# tiny84standalone.net
KiCad netlist of a schematic drawn in EAGLE
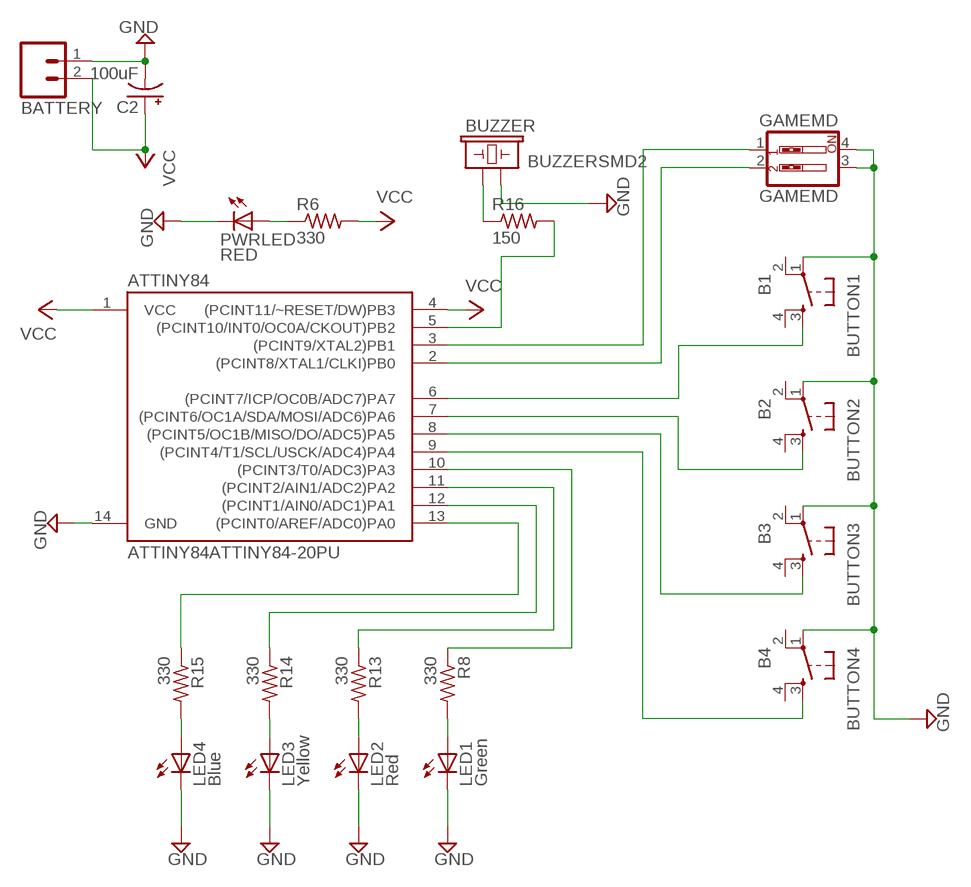
[diagram p0: schematic, sheet 1]

(export (version "E")
  (design (tool "Eeschema 10.0.6"))
  (components
    (comp (ref "ATTINY84")
      (value "ATTINY84ATTINY84-20PU")
      (footprint "eagle-import:DIL14")
      (libsource (lib "eagle-import") (part "ATTINY84ATTINY84-20PU"))
    )
    (comp (ref "BATTERY")
      (value "M02JST-PTH-VERT")
      (footprint "eagle-import:JST-2-PTH-VERT")
      (libsource (lib "eagle-import") (part "M02JST-PTH-VERT"))
    )
    (comp (ref "BUTTON1")
      (value "B1")
      (footprint "eagle-import:TACTILE-PTH")
      (libsource (lib "eagle-import") (part "TAC_SWITCHPTH"))
    )
    (comp (ref "BUTTON2")
      (value "B2")
      (footprint "eagle-import:TACTILE-PTH")
      (libsource (lib "eagle-import") (part "TAC_SWITCHPTH"))
    )
    (comp (ref "BUTTON3")
      (value "B3")
      (footprint "eagle-import:TACTILE-PTH")
      (libsource (lib "eagle-import") (part "TAC_SWITCHPTH"))
    )
    (comp (ref "BUTTON4")
      (value "B4")
      (footprint "eagle-import:TACTILE-PTH")
      (libsource (lib "eagle-import") (part "TAC_SWITCHPTH"))
    )
    (comp (ref "BUZZER")
      (value "BUZZERSMD2")
      (footprint "eagle-import:BUZZER-CCV")
      (libsource (lib "eagle-import") (part "BUZZERSMD2"))
    )
    (comp (ref "C2")
      (value "100uF")
      (footprint "eagle-import:CPOL-RADIAL-100UF-25V")
      (libsource (lib "eagle-import") (part "CAP_POLPTH1"))
    )
    (comp (ref "GAMEMD")
      (value "GAMEMD")
      (footprint "eagle-import:DIPSWITCH-02")
      (libsource (lib "eagle-import") (part "SW_DIP-2"))
    )
    (comp (ref "LED1")
      (value "Green")
      (footprint "eagle-import:LED5MM")
      (libsource (lib "eagle-import") (part "LED5MM"))
    )
    (comp (ref "LED2")
      (value "Red")
      (footprint "eagle-import:LED5MM")
      (libsource (lib "eagle-import") (part "LED5MM"))
    )
    (comp (ref "LED3")
      (value "Yellow")
      (footprint "eagle-import:LED5MM")
      (libsource (lib "eagle-import") (part "LED5MM"))
    )
    (comp (ref "LED4")
      (value "Blue")
      (footprint "eagle-import:LED5MM")
      (libsource (lib "eagle-import") (part "LED5MM"))
    )
    (comp (ref "PWRLED")
      (value "RED")
      (footprint "eagle-import:CHIPLED_0805")
      (libsource (lib "eagle-import") (part "LEDCHIPLED_0805"))
    )
    (comp (ref "R6")
      (value "330")
      (footprint "eagle-import:R0805")
      (libsource (lib "eagle-import") (part "resistor_R-US_R0805"))
    )
    (comp (ref "R8")
      (value "330")
      (footprint "eagle-import:R0805")
      (libsource (lib "eagle-import") (part "R-US_R0805"))
    )
    (comp (ref "R13")
      (value "330")
      (footprint "eagle-import:R0805")
      (libsource (lib "eagle-import") (part "R-US_R0805"))
    )
    (comp (ref "R14")
      (value "330")
      (footprint "eagle-import:R0805")
      (libsource (lib "eagle-import") (part "R-US_R0805"))
    )
    (comp (ref "R15")
      (value "330")
      (footprint "eagle-import:R0805")
      (libsource (lib "eagle-import") (part "R-US_R0805"))
    )
    (comp (ref "R16")
      (value "150")
      (footprint "eagle-import:R0805")
      (libsource (lib "eagle-import") (part "resistor_R-US_R0805"))
    )
  )
  (nets
    (net (code "1") (name "GND") (class "Default")
      (node (ref "ATTINY84") (pin "14") (pinfunction "GND_14") (pintype "bidirectional"))
      (node (ref "BATTERY") (pin "1") (pinfunction "1_1") (pintype "passive"))
      (node (ref "BUTTON1") (pin "1") (pinfunction "1_1") (pintype "passive"))
      (node (ref "BUTTON2") (pin "1") (pinfunction "1_1") (pintype "passive"))
      (node (ref "BUTTON3") (pin "1") (pinfunction "1_1") (pintype "passive"))
      (node (ref "BUTTON4") (pin "1") (pinfunction "1_1") (pintype "passive"))
      (node (ref "BUZZER") (pin "-") (pinfunction "2_-") (pintype "passive"))
      (node (ref "C2") (pin "2") (pinfunction "-_2") (pintype "passive"))
      (node (ref "GAMEMD") (pin "3") (pinfunction "3_3") (pintype "passive"))
      (node (ref "GAMEMD") (pin "4") (pinfunction "4_4") (pintype "passive"))
      (node (ref "LED1") (pin "K") (pinfunction "C_K") (pintype "passive"))
      (node (ref "LED2") (pin "K") (pinfunction "C_K") (pintype "passive"))
      (node (ref "LED3") (pin "K") (pinfunction "C_K") (pintype "passive"))
      (node (ref "LED4") (pin "K") (pinfunction "C_K") (pintype "passive"))
      (node (ref "PWRLED") (pin "C") (pinfunction "C_C") (pintype "passive"))
    )
    (net (code "2") (name "Net-(ATTINY84-(PCINT0{slash}AREF{slash}ADC0)PA0)") (class "Default")
      (node (ref "ATTINY84") (pin "13") (pinfunction "(PCINT0/AREF/ADC0)PA0_13") (pintype "bidirectional"))
      (node (ref "R15") (pin "1") (pinfunction "1_1") (pintype "passive"))
    )
    (net (code "3") (name "Net-(ATTINY84-(PCINT1{slash}AIN0{slash}ADC1)PA1)") (class "Default")
      (node (ref "ATTINY84") (pin "12") (pinfunction "(PCINT1/AIN0/ADC1)PA1_12") (pintype "bidirectional"))
      (node (ref "R14") (pin "1") (pinfunction "1_1") (pintype "passive"))
    )
    (net (code "4") (name "Net-(ATTINY84-(PCINT2{slash}AIN1{slash}ADC2)PA2)") (class "Default")
      (node (ref "ATTINY84") (pin "11") (pinfunction "(PCINT2/AIN1/ADC2)PA2_11") (pintype "bidirectional"))
      (node (ref "R13") (pin "1") (pinfunction "1_1") (pintype "passive"))
    )
    (net (code "5") (name "Net-(ATTINY84-(PCINT3{slash}T0{slash}ADC3)PA3)") (class "Default")
      (node (ref "ATTINY84") (pin "10") (pinfunction "(PCINT3/T0/ADC3)PA3_10") (pintype "bidirectional"))
      (node (ref "R8") (pin "1") (pinfunction "1_1") (pintype "passive"))
    )
    (net (code "6") (name "Net-(ATTINY84-(PCINT4{slash}T1{slash}SCL{slash}USCK{slash}ADC4)PA4)") (class "Default")
      (node (ref "ATTINY84") (pin "9") (pinfunction "(PCINT4/T1/SCL/USCK/ADC4)PA4_9") (pintype "bidirectional"))
      (node (ref "BUTTON4") (pin "3") (pinfunction "3_3") (pintype "passive"))
    )
    (net (code "7") (name "Net-(ATTINY84-(PCINT5{slash}OC1B{slash}MISO{slash}DO{slash}ADC5)PA5)") (class "Default")
      (node (ref "ATTINY84") (pin "8") (pinfunction "(PCINT5/OC1B/MISO/DO/ADC5)PA5_8") (pintype "bidirectional"))
      (node (ref "BUTTON3") (pin "3") (pinfunction "3_3") (pintype "passive"))
    )
    (net (code "8") (name "Net-(ATTINY84-(PCINT6{slash}OC1A{slash}SDA{slash}MOSI{slash}ADC6)PA6)") (class "Default")
      (node (ref "ATTINY84") (pin "7") (pinfunction "(PCINT6/OC1A/SDA/MOSI/ADC6)PA6_7") (pintype "bidirectional"))
      (node (ref "BUTTON2") (pin "3") (pinfunction "3_3") (pintype "passive"))
    )
    (net (code "9") (name "Net-(ATTINY84-(PCINT7{slash}ICP{slash}OC0B{slash}ADC7)PA7)") (class "Default")
      (node (ref "ATTINY84") (pin "6") (pinfunction "(PCINT7/ICP/OC0B/ADC7)PA7_6") (pintype "bidirectional"))
      (node (ref "BUTTON1") (pin "3") (pinfunction "3_3") (pintype "passive"))
    )
    (net (code "10") (name "Net-(ATTINY84-(PCINT8{slash}XTAL1{slash}CLKI)PB0)") (class "Default")
      (node (ref "ATTINY84") (pin "2") (pinfunction "(PCINT8/XTAL1/CLKI)PB0_2") (pintype "bidirectional"))
      (node (ref "GAMEMD") (pin "2") (pinfunction "2_2") (pintype "passive"))
    )
    (net (code "11") (name "Net-(ATTINY84-(PCINT9{slash}XTAL2)PB1)") (class "Default")
      (node (ref "ATTINY84") (pin "3") (pinfunction "(PCINT9/XTAL2)PB1_3") (pintype "bidirectional"))
      (node (ref "GAMEMD") (pin "1") (pinfunction "1_1") (pintype "passive"))
    )
    (net (code "12") (name "Net-(ATTINY84-(PCINT10{slash}INT0{slash}OC0A{slash}CKOUT)PB2)") (class "Default")
      (node (ref "ATTINY84") (pin "5") (pinfunction "(PCINT10/INT0/OC0A/CKOUT)PB2_5") (pintype "bidirectional"))
      (node (ref "R16") (pin "2") (pinfunction "2_2") (pintype "passive"))
    )
    (net (code "13") (name "Net-(BUZZER-1)") (class "Default")
      (node (ref "BUZZER") (pin "+") (pinfunction "1_+") (pintype "passive"))
      (node (ref "R16") (pin "1") (pinfunction "1_1") (pintype "passive"))
    )
    (net (code "14") (name "Net-(LED1-PadA)") (class "Default")
      (node (ref "LED1") (pin "A") (pinfunction "A_A") (pintype "passive"))
      (node (ref "R8") (pin "2") (pinfunction "2_2") (pintype "passive"))
    )
    (net (code "15") (name "Net-(LED2-PadA)") (class "Default")
      (node (ref "LED2") (pin "A") (pinfunction "A_A") (pintype "passive"))
      (node (ref "R13") (pin "2") (pinfunction "2_2") (pintype "passive"))
    )
    (net (code "16") (name "Net-(LED3-PadA)") (class "Default")
      (node (ref "LED3") (pin "A") (pinfunction "A_A") (pintype "passive"))
      (node (ref "R14") (pin "2") (pinfunction "2_2") (pintype "passive"))
    )
    (net (code "17") (name "Net-(LED4-PadA)") (class "Default")
      (node (ref "LED4") (pin "A") (pinfunction "A_A") (pintype "passive"))
      (node (ref "R15") (pin "2") (pinfunction "2_2") (pintype "passive"))
    )
    (net (code "18") (name "Net-(PWRLED-PadA)") (class "Default")
      (node (ref "PWRLED") (pin "A") (pinfunction "A_A") (pintype "passive"))
      (node (ref "R6") (pin "1") (pinfunction "1_1") (pintype "passive"))
    )
    (net (code "19") (name "VCC") (class "Default")
      (node (ref "ATTINY84") (pin "1") (pinfunction "VCC_1") (pintype "bidirectional"))
      (node (ref "ATTINY84") (pin "4") (pinfunction "(PCINT11/~{RESET/DW})PB3_4") (pintype "bidirectional"))
      (node (ref "BATTERY") (pin "2") (pinfunction "2_2") (pintype "passive"))
      (node (ref "C2") (pin "1") (pinfunction "+_1") (pintype "passive"))
      (node (ref "R6") (pin "2") (pinfunction "2_2") (pintype "passive"))
    )
    (net (code "20") (name "unconnected-(BUTTON1-Pad2)") (class "Default")
      (node (ref "BUTTON1") (pin "2") (pinfunction "2_2") (pintype "passive"))
    )
    (net (code "21") (name "unconnected-(BUTTON1-Pad4)") (class "Default")
      (node (ref "BUTTON1") (pin "4") (pinfunction "4_4") (pintype "passive"))
    )
    (net (code "22") (name "unconnected-(BUTTON2-Pad2)") (class "Default")
      (node (ref "BUTTON2") (pin "2") (pinfunction "2_2") (pintype "passive"))
    )
    (net (code "23") (name "unconnected-(BUTTON2-Pad4)") (class "Default")
      (node (ref "BUTTON2") (pin "4") (pinfunction "4_4") (pintype "passive"))
    )
    (net (code "24") (name "unconnected-(BUTTON3-Pad2)") (class "Default")
      (node (ref "BUTTON3") (pin "2") (pinfunction "2_2") (pintype "passive"))
    )
    (net (code "25") (name "unconnected-(BUTTON3-Pad4)") (class "Default")
      (node (ref "BUTTON3") (pin "4") (pinfunction "4_4") (pintype "passive"))
    )
    (net (code "26") (name "unconnected-(BUTTON4-Pad2)") (class "Default")
      (node (ref "BUTTON4") (pin "2") (pinfunction "2_2") (pintype "passive"))
    )
    (net (code "27") (name "unconnected-(BUTTON4-Pad4)") (class "Default")
      (node (ref "BUTTON4") (pin "4") (pinfunction "4_4") (pintype "passive"))
    )
  )
)
